# TEC-Controller.net
KiCad netlist of a schematic drawn in EAGLE
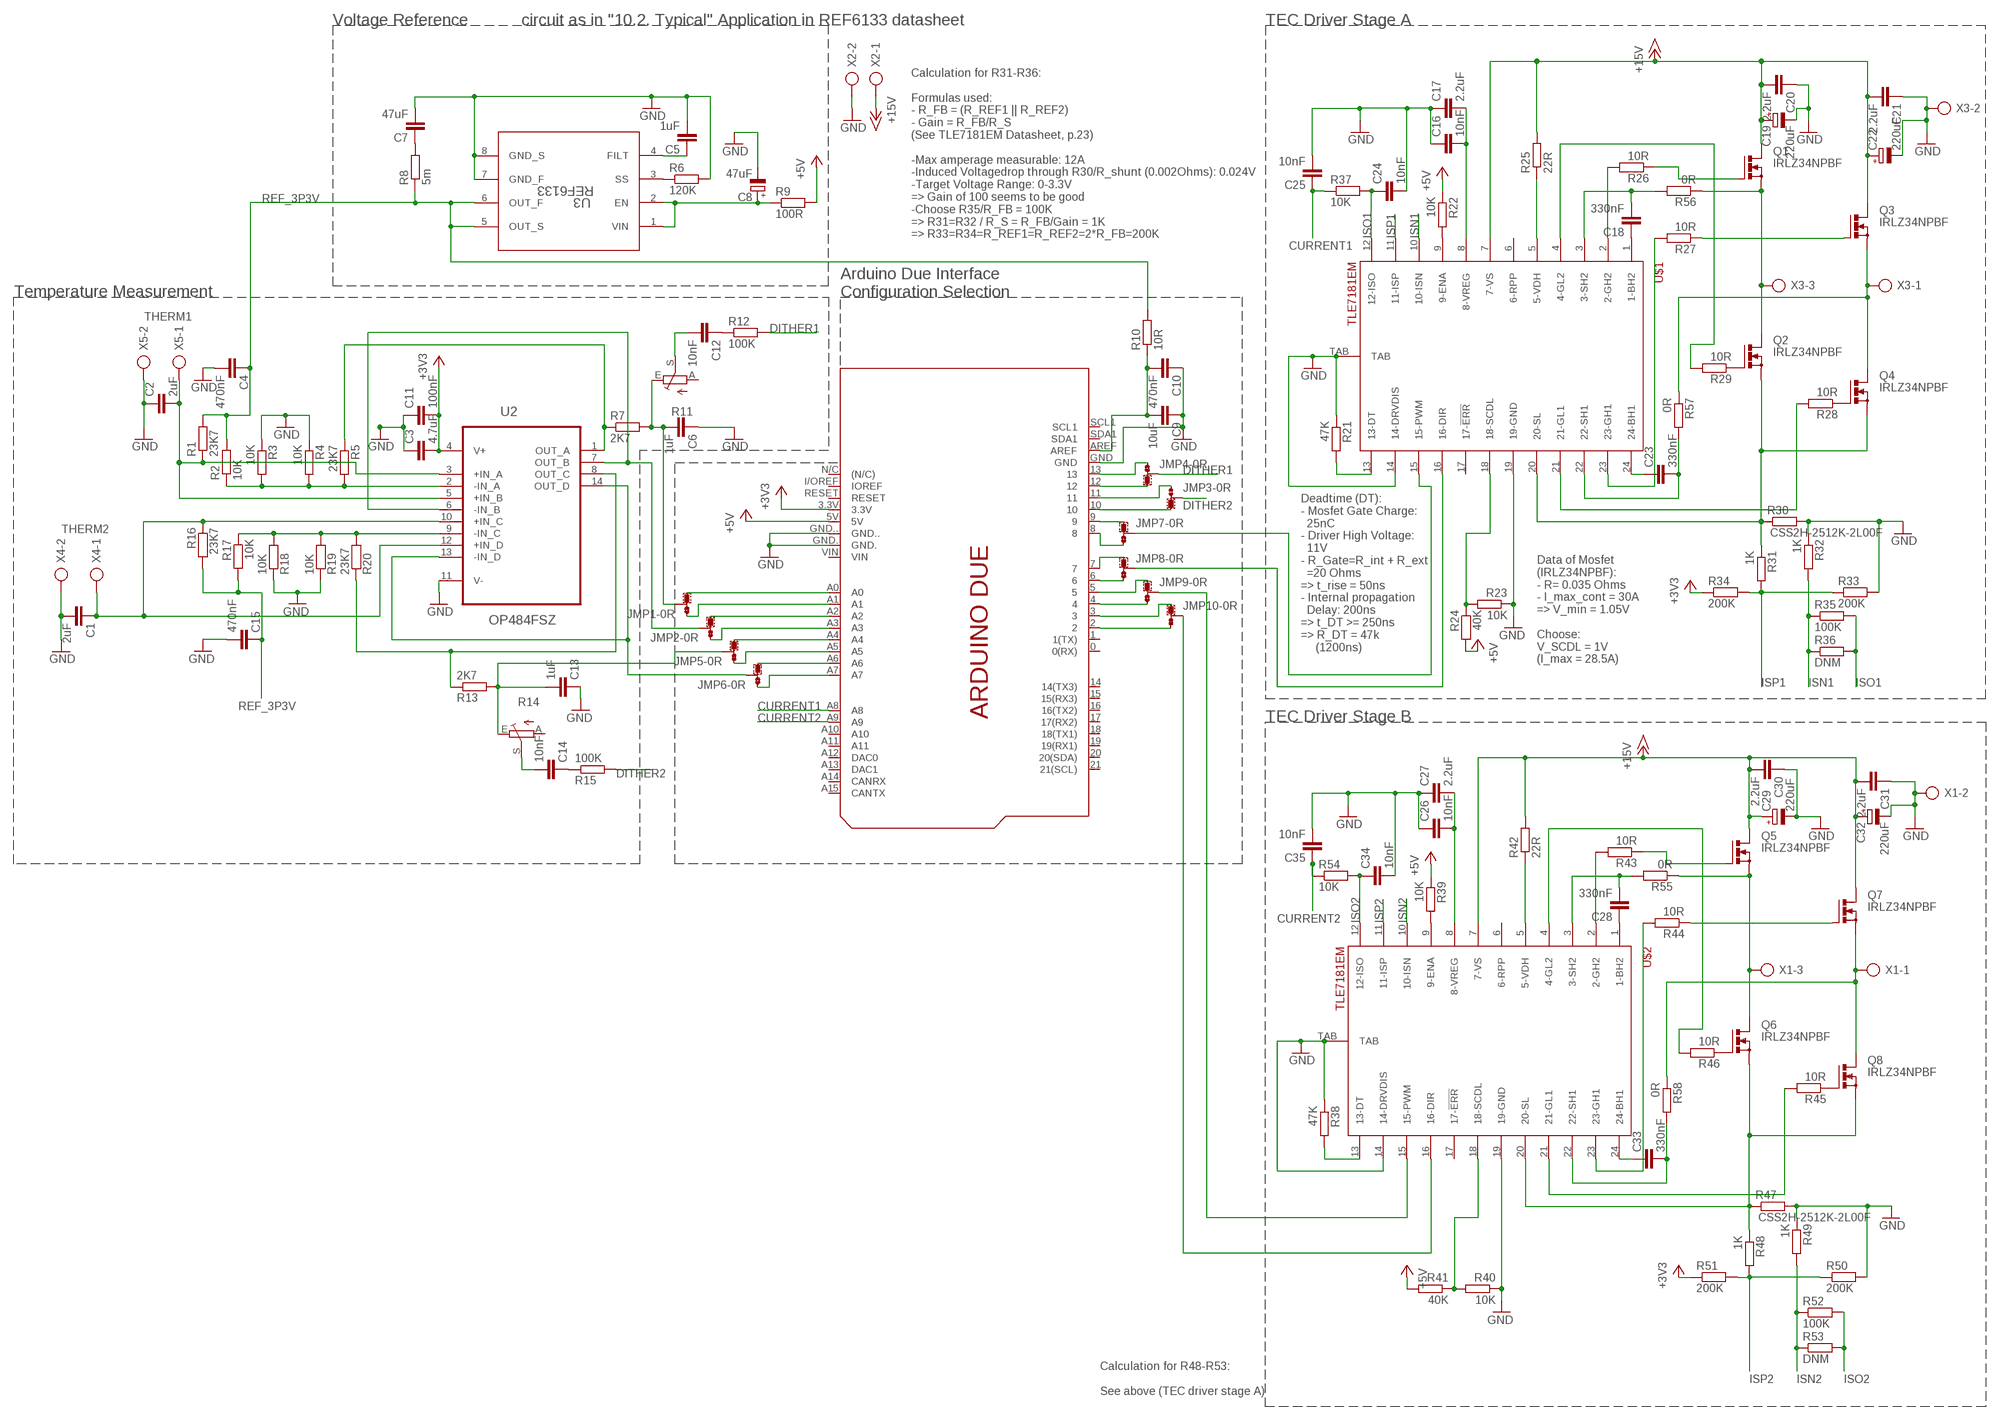
[diagram p0: schematic, sheet 1]

(export (version "E")
  (design (tool "Eeschema 10.0.6"))
  (components
    (comp (ref "C1")
      (value "2uF")
      (footprint "eagle-import:C0805")
      (libsource (lib "eagle-import") (part "C-EUC0805"))
    )
    (comp (ref "C2")
      (value "2uF")
      (footprint "eagle-import:C0805")
      (libsource (lib "eagle-import") (part "C-EUC0805"))
    )
    (comp (ref "C3")
      (value "4.7uF")
      (footprint "eagle-import:C0603")
      (libsource (lib "eagle-import") (part "C-EUC0603"))
    )
    (comp (ref "C4")
      (value "470nF")
      (footprint "eagle-import:C0805")
      (libsource (lib "eagle-import") (part "C-EUC0805"))
    )
    (comp (ref "C5")
      (value "1uF")
      (footprint "eagle-import:C0805")
      (libsource (lib "eagle-import") (part "C-EUC0805"))
    )
    (comp (ref "C6")
      (value "1uF")
      (footprint "eagle-import:C0805")
      (libsource (lib "eagle-import") (part "C-EUC0805"))
    )
    (comp (ref "C7")
      (value "47uF")
      (footprint "eagle-import:C0603")
      (libsource (lib "eagle-import") (part "C-EUC0603"))
    )
    (comp (ref "C8")
      (value "47uF")
      (footprint "eagle-import:PANASONIC_D")
      (libsource (lib "eagle-import") (part "CPOL-EUD"))
    )
    (comp (ref "C9")
      (value "10uF")
      (footprint "eagle-import:C0603")
      (libsource (lib "eagle-import") (part "C-EUC0603"))
    )
    (comp (ref "C10")
      (value "470nF")
      (footprint "eagle-import:C0603")
      (libsource (lib "eagle-import") (part "C-EUC0603"))
    )
    (comp (ref "C11")
      (value "100nF")
      (footprint "eagle-import:C0603")
      (libsource (lib "eagle-import") (part "C-EUC0603"))
    )
    (comp (ref "C12")
      (value "10nF")
      (footprint "eagle-import:C0805")
      (libsource (lib "eagle-import") (part "C-EUC0805"))
    )
    (comp (ref "C13")
      (value "1uF")
      (footprint "eagle-import:C0805")
      (libsource (lib "eagle-import") (part "C-EUC0805"))
    )
    (comp (ref "C14")
      (value "10nF")
      (footprint "eagle-import:C0805")
      (libsource (lib "eagle-import") (part "C-EUC0805"))
    )
    (comp (ref "C15")
      (value "470nF")
      (footprint "eagle-import:C0603")
      (libsource (lib "eagle-import") (part "C-EUC0603"))
    )
    (comp (ref "C16")
      (value "10nF")
      (footprint "eagle-import:C0603K")
      (libsource (lib "eagle-import") (part "C-EUC0603K"))
    )
    (comp (ref "C17")
      (value "2.2uF")
      (footprint "eagle-import:C0603K")
      (libsource (lib "eagle-import") (part "C-EUC0603K"))
    )
    (comp (ref "C18")
      (value "330nF")
      (footprint "eagle-import:C0603K")
      (libsource (lib "eagle-import") (part "C-EUC0603K"))
    )
    (comp (ref "C19")
      (value "220uF")
      (footprint "eagle-import:E2,5-7")
      (libsource (lib "eagle-import") (part "CPOL-EUE2.5-7"))
    )
    (comp (ref "C20")
      (value "2.2uF")
      (footprint "eagle-import:C0603K")
      (libsource (lib "eagle-import") (part "C-EUC0603K"))
    )
    (comp (ref "C21")
      (value "2.2uF")
      (footprint "eagle-import:C0603K")
      (libsource (lib "eagle-import") (part "C-EUC0603K"))
    )
    (comp (ref "C22")
      (value "220uF")
      (footprint "eagle-import:E2,5-7")
      (libsource (lib "eagle-import") (part "CPOL-EUE2.5-7"))
    )
    (comp (ref "C23")
      (value "330nF")
      (footprint "eagle-import:C0603K")
      (libsource (lib "eagle-import") (part "C-EUC0603K"))
    )
    (comp (ref "C24")
      (value "10nF")
      (footprint "eagle-import:C0603K")
      (libsource (lib "eagle-import") (part "C-EUC0603K"))
    )
    (comp (ref "C25")
      (value "10nF")
      (footprint "eagle-import:C0603K")
      (libsource (lib "eagle-import") (part "C-EUC0603K"))
    )
    (comp (ref "C26")
      (value "10nF")
      (footprint "eagle-import:C0603")
      (libsource (lib "eagle-import") (part "C-EUC0603"))
    )
    (comp (ref "C27")
      (value "2.2uF")
      (footprint "eagle-import:C0603")
      (libsource (lib "eagle-import") (part "C-EUC0603"))
    )
    (comp (ref "C28")
      (value "330nF")
      (footprint "eagle-import:C0603K")
      (libsource (lib "eagle-import") (part "C-EUC0603K"))
    )
    (comp (ref "C29")
      (value "220uF")
      (footprint "eagle-import:E2,5-7")
      (libsource (lib "eagle-import") (part "CPOL-EUE2.5-7"))
    )
    (comp (ref "C30")
      (value "2.2uF")
      (footprint "eagle-import:C0603K")
      (libsource (lib "eagle-import") (part "C-EUC0603K"))
    )
    (comp (ref "C31")
      (value "2.2uF")
      (footprint "eagle-import:C0603K")
      (libsource (lib "eagle-import") (part "C-EUC0603K"))
    )
    (comp (ref "C32")
      (value "220uF")
      (footprint "eagle-import:E2,5-7")
      (libsource (lib "eagle-import") (part "CPOL-EUE2.5-7"))
    )
    (comp (ref "C33")
      (value "330nF")
      (footprint "eagle-import:C0603K")
      (libsource (lib "eagle-import") (part "C-EUC0603K"))
    )
    (comp (ref "C34")
      (value "10nF")
      (footprint "eagle-import:C0603")
      (libsource (lib "eagle-import") (part "C-EUC0603"))
    )
    (comp (ref "C35")
      (value "10nF")
      (footprint "eagle-import:C0603")
      (libsource (lib "eagle-import") (part "C-EUC0603"))
    )
    (comp (ref "JMP1")
      (value "0R-JUMPA")
      (footprint "eagle-import:A0R-JMP")
      (libsource (lib "eagle-import") (part "0R-JUMPA"))
    )
    (comp (ref "JMP2")
      (value "0R-JUMPA")
      (footprint "eagle-import:A0R-JMP")
      (libsource (lib "eagle-import") (part "0R-JUMPA"))
    )
    (comp (ref "JMP3")
      (value "0R-JUMPA")
      (footprint "eagle-import:A0R-JMP")
      (libsource (lib "eagle-import") (part "0R-JUMPA"))
    )
    (comp (ref "JMP4")
      (value "0R-JUMPA")
      (footprint "eagle-import:A0R-JMP")
      (libsource (lib "eagle-import") (part "0R-JUMPA"))
    )
    (comp (ref "JMP5")
      (value "0R-JUMPA")
      (footprint "eagle-import:A0R-JMP")
      (libsource (lib "eagle-import") (part "0R-JUMPA"))
    )
    (comp (ref "JMP6")
      (value "0R-JUMPA")
      (footprint "eagle-import:A0R-JMP")
      (libsource (lib "eagle-import") (part "0R-JUMPA"))
    )
    (comp (ref "JMP7")
      (value "0R-JUMPA")
      (footprint "eagle-import:A0R-JMP")
      (libsource (lib "eagle-import") (part "0R-JUMPA"))
    )
    (comp (ref "JMP8")
      (value "0R-JUMPA")
      (footprint "eagle-import:A0R-JMP")
      (libsource (lib "eagle-import") (part "0R-JUMPA"))
    )
    (comp (ref "JMP9")
      (value "0R-JUMPA")
      (footprint "eagle-import:A0R-JMP")
      (libsource (lib "eagle-import") (part "0R-JUMPA"))
    )
    (comp (ref "JMP10")
      (value "0R-JUMPA")
      (footprint "eagle-import:A0R-JMP")
      (libsource (lib "eagle-import") (part "0R-JUMPA"))
    )
    (comp (ref "PCB1")
      (value "ARDUINO_DUE_SHIELD")
      (footprint "eagle-import:ARDUINO_DUE_SHIELD")
      (libsource (lib "eagle-import") (part "ARDUINO_DUE_SHIELD"))
    )
    (comp (ref "Q1")
      (value "IRLZ34NPBF")
      (footprint "eagle-import:TO220BV")
      (libsource (lib "eagle-import") (part "PMOSFET_NTO220BV"))
    )
    (comp (ref "Q2")
      (value "IRLZ34NPBF")
      (footprint "eagle-import:TO220BV")
      (libsource (lib "eagle-import") (part "PMOSFET_NTO220BV"))
    )
    (comp (ref "Q3")
      (value "IRLZ34NPBF")
      (footprint "eagle-import:TO220BV")
      (libsource (lib "eagle-import") (part "PMOSFET_NTO220BV"))
    )
    (comp (ref "Q4")
      (value "IRLZ34NPBF")
      (footprint "eagle-import:TO220BV")
      (libsource (lib "eagle-import") (part "PMOSFET_NTO220BV"))
    )
    (comp (ref "Q5")
      (value "IRLZ34NPBF")
      (footprint "eagle-import:TO220BV")
      (libsource (lib "eagle-import") (part "PMOSFET_NTO220BV"))
    )
    (comp (ref "Q6")
      (value "IRLZ34NPBF")
      (footprint "eagle-import:TO220BV")
      (libsource (lib "eagle-import") (part "PMOSFET_NTO220BV"))
    )
    (comp (ref "Q7")
      (value "IRLZ34NPBF")
      (footprint "eagle-import:TO220BV")
      (libsource (lib "eagle-import") (part "PMOSFET_NTO220BV"))
    )
    (comp (ref "Q8")
      (value "IRLZ34NPBF")
      (footprint "eagle-import:TO220BV")
      (libsource (lib "eagle-import") (part "PMOSFET_NTO220BV"))
    )
    (comp (ref "R1")
      (value "23K7")
      (footprint "eagle-import:R0603")
      (libsource (lib "eagle-import") (part "R-EU_R0603"))
    )
    (comp (ref "R2")
      (value "10K")
      (footprint "eagle-import:R0603")
      (libsource (lib "eagle-import") (part "R-EU_R0603"))
    )
    (comp (ref "R3")
      (value "10K")
      (footprint "eagle-import:R0603")
      (libsource (lib "eagle-import") (part "R-EU_R0603"))
    )
    (comp (ref "R4")
      (value "10K")
      (footprint "eagle-import:R0805")
      (libsource (lib "eagle-import") (part "R-EU_R0805"))
    )
    (comp (ref "R5")
      (value "23K7")
      (footprint "eagle-import:R0805")
      (libsource (lib "eagle-import") (part "R-EU_R0805"))
    )
    (comp (ref "R6")
      (value "120K")
      (footprint "eagle-import:R0805")
      (libsource (lib "eagle-import") (part "R-EU_R0805"))
    )
    (comp (ref "R7")
      (value "2K7")
      (footprint "eagle-import:R0805")
      (libsource (lib "eagle-import") (part "R-EU_R0805"))
    )
    (comp (ref "R8")
      (value "5m")
      (footprint "eagle-import:R0603")
      (libsource (lib "eagle-import") (part "R-EU_R0603"))
    )
    (comp (ref "R9")
      (value "100R")
      (footprint "eagle-import:R0805")
      (libsource (lib "eagle-import") (part "R-EU_R0805"))
    )
    (comp (ref "R10")
      (value "10R")
      (footprint "eagle-import:R0805")
      (libsource (lib "eagle-import") (part "R-EU_R0805"))
    )
    (comp (ref "R11")
      (value "TRIM_EU-B64W")
      (footprint "eagle-import:B64W")
      (libsource (lib "eagle-import") (part "TRIM_EU-B64W"))
    )
    (comp (ref "R12")
      (value "100K")
      (footprint "eagle-import:R0805")
      (libsource (lib "eagle-import") (part "R-EU_R0805"))
    )
    (comp (ref "R13")
      (value "2K7")
      (footprint "eagle-import:R0805")
      (libsource (lib "eagle-import") (part "R-EU_R0805"))
    )
    (comp (ref "R14")
      (value "TRIM_EU-B64W")
      (footprint "eagle-import:B64W")
      (libsource (lib "eagle-import") (part "TRIM_EU-B64W"))
    )
    (comp (ref "R15")
      (value "100K")
      (footprint "eagle-import:R0805")
      (libsource (lib "eagle-import") (part "R-EU_R0805"))
    )
    (comp (ref "R16")
      (value "23K7")
      (footprint "eagle-import:R0805")
      (libsource (lib "eagle-import") (part "R-EU_R0805"))
    )
    (comp (ref "R17")
      (value "10K")
      (footprint "eagle-import:R0805")
      (libsource (lib "eagle-import") (part "R-EU_R0805"))
    )
    (comp (ref "R18")
      (value "10K")
      (footprint "eagle-import:R0805")
      (libsource (lib "eagle-import") (part "R-EU_R0805"))
    )
    (comp (ref "R19")
      (value "10K")
      (footprint "eagle-import:R0805")
      (libsource (lib "eagle-import") (part "R-EU_R0805"))
    )
    (comp (ref "R20")
      (value "23K7")
      (footprint "eagle-import:R0805")
      (libsource (lib "eagle-import") (part "R-EU_R0805"))
    )
    (comp (ref "R21")
      (value "47K")
      (footprint "eagle-import:R0603")
      (libsource (lib "eagle-import") (part "R-EU_R0603"))
    )
    (comp (ref "R22")
      (value "10K")
      (footprint "eagle-import:R0603")
      (libsource (lib "eagle-import") (part "R-EU_R0603"))
    )
    (comp (ref "R23")
      (value "10K")
      (footprint "eagle-import:R0603")
      (libsource (lib "eagle-import") (part "R-EU_R0603"))
    )
    (comp (ref "R24")
      (value "40K")
      (footprint "eagle-import:R0603")
      (libsource (lib "eagle-import") (part "R-EU_R0603"))
    )
    (comp (ref "R25")
      (value "22R")
      (footprint "eagle-import:R0603")
      (libsource (lib "eagle-import") (part "R-EU_R0603"))
    )
    (comp (ref "R26")
      (value "10R")
      (footprint "eagle-import:R0805")
      (libsource (lib "eagle-import") (part "R-EU_R0805"))
    )
    (comp (ref "R27")
      (value "10R")
      (footprint "eagle-import:0204_7")
      (libsource (lib "eagle-import") (part "R-EU_0204/7"))
    )
    (comp (ref "R28")
      (value "10R")
      (footprint "eagle-import:0204_7")
      (libsource (lib "eagle-import") (part "R-EU_0204/7"))
    )
    (comp (ref "R29")
      (value "10R")
      (footprint "eagle-import:0204_7")
      (libsource (lib "eagle-import") (part "R-EU_0204/7"))
    )
    (comp (ref "R30")
      (value "CSS2H-2512K-2L00F")
      (footprint "eagle-import:R2512")
      (libsource (lib "eagle-import") (part "R-EU_R2512"))
    )
    (comp (ref "R31")
      (value "1K")
      (footprint "eagle-import:R0603")
      (libsource (lib "eagle-import") (part "R-EU_R0603"))
    )
    (comp (ref "R32")
      (value "1K")
      (footprint "eagle-import:R0603")
      (libsource (lib "eagle-import") (part "R-EU_R0603"))
    )
    (comp (ref "R33")
      (value "200K")
      (footprint "eagle-import:R0603")
      (libsource (lib "eagle-import") (part "R-EU_R0603"))
    )
    (comp (ref "R34")
      (value "200K")
      (footprint "eagle-import:R0603")
      (libsource (lib "eagle-import") (part "R-EU_R0603"))
    )
    (comp (ref "R35")
      (value "100K")
      (footprint "eagle-import:R0603")
      (libsource (lib "eagle-import") (part "R-EU_R0603"))
    )
    (comp (ref "R36")
      (value "DNM")
      (footprint "eagle-import:R0603")
      (libsource (lib "eagle-import") (part "R-EU_R0603"))
    )
    (comp (ref "R37")
      (value "10K")
      (footprint "eagle-import:R0603")
      (libsource (lib "eagle-import") (part "R-EU_R0603"))
    )
    (comp (ref "R38")
      (value "47K")
      (footprint "eagle-import:R0603")
      (libsource (lib "eagle-import") (part "R-EU_R0603"))
    )
    (comp (ref "R39")
      (value "10K")
      (footprint "eagle-import:R0603")
      (libsource (lib "eagle-import") (part "R-EU_R0603"))
    )
    (comp (ref "R40")
      (value "10K")
      (footprint "eagle-import:R0603")
      (libsource (lib "eagle-import") (part "R-EU_R0603"))
    )
    (comp (ref "R41")
      (value "40K")
      (footprint "eagle-import:R0603")
      (libsource (lib "eagle-import") (part "R-EU_R0603"))
    )
    (comp (ref "R42")
      (value "22R")
      (footprint "eagle-import:R0603")
      (libsource (lib "eagle-import") (part "R-EU_R0603"))
    )
    (comp (ref "R43")
      (value "10R")
      (footprint "eagle-import:0204_7")
      (libsource (lib "eagle-import") (part "R-EU_0204/7"))
    )
    (comp (ref "R44")
      (value "10R")
      (footprint "eagle-import:0204_7")
      (libsource (lib "eagle-import") (part "R-EU_0204/7"))
    )
    (comp (ref "R45")
      (value "10R")
      (footprint "eagle-import:0204_7")
      (libsource (lib "eagle-import") (part "R-EU_0204/7"))
    )
    (comp (ref "R46")
      (value "10R")
      (footprint "eagle-import:0204_7")
      (libsource (lib "eagle-import") (part "R-EU_0204/7"))
    )
    (comp (ref "R47")
      (value "CSS2H-2512K-2L00F")
      (footprint "eagle-import:R2512")
      (libsource (lib "eagle-import") (part "R-EU_R2512"))
    )
    (comp (ref "R48")
      (value "1K")
      (footprint "eagle-import:R0603")
      (libsource (lib "eagle-import") (part "R-EU_R0603"))
    )
    (comp (ref "R49")
      (value "1K")
      (footprint "eagle-import:R0603")
      (libsource (lib "eagle-import") (part "R-EU_R0603"))
    )
    (comp (ref "R50")
      (value "200K")
      (footprint "eagle-import:R0603")
      (libsource (lib "eagle-import") (part "R-EU_R0603"))
    )
    (comp (ref "R51")
      (value "200K")
      (footprint "eagle-import:R0603")
      (libsource (lib "eagle-import") (part "R-EU_R0603"))
    )
    (comp (ref "R52")
      (value "100K")
      (footprint "eagle-import:R0603")
      (libsource (lib "eagle-import") (part "R-EU_R0603"))
    )
    (comp (ref "R53")
      (value "DNM")
      (footprint "eagle-import:R0603")
      (libsource (lib "eagle-import") (part "R-EU_R0603"))
    )
    (comp (ref "R54")
      (value "10K")
      (footprint "eagle-import:R0603")
      (libsource (lib "eagle-import") (part "R-EU_R0603"))
    )
    (comp (ref "R55")
      (value "0R")
      (footprint "eagle-import:0204_7")
      (libsource (lib "eagle-import") (part "R-EU_0204/7"))
    )
    (comp (ref "R56")
      (value "0R")
      (footprint "eagle-import:0204_7")
      (libsource (lib "eagle-import") (part "R-EU_0204/7"))
    )
    (comp (ref "R57")
      (value "0R")
      (footprint "eagle-import:0204_7")
      (libsource (lib "eagle-import") (part "R-EU_0204/7"))
    )
    (comp (ref "R58")
      (value "0R")
      (footprint "eagle-import:0204_7")
      (libsource (lib "eagle-import") (part "R-EU_0204/7"))
    )
    (comp (ref "U$1")
      (value "TLE7181EM")
      (footprint "eagle-import:PG-SSOP-24-4")
      (libsource (lib "eagle-import") (part "TLE7181EM"))
    )
    (comp (ref "U$2")
      (value "TLE7181EM")
      (footprint "eagle-import:PG-SSOP-24-4")
      (libsource (lib "eagle-import") (part "TLE7181EM"))
    )
    (comp (ref "U2")
      (value "OP484FSZ")
      (footprint "eagle-import:SOIC127P600X175-14N")
      (libsource (lib "eagle-import") (part "OP484FSZ"))
    )
    (comp (ref "U3")
      (value "REF6133")
      (footprint "eagle-import:DGK0008A_N")
      (fields (field (name "MANUFACTURER") "Texas Instruments") (field (name "PARTNUMBER") "REF6033IDGKR"))
      (libsource (lib "eagle-import") (part "REF6033IDGKR"))
    )
    (comp (ref "X1")
      (value "AK500/3")
      (footprint "eagle-import:AK500_3")
      (libsource (lib "eagle-import") (part "AK500/3"))
    )
    (comp (ref "X2")
      (value "AK500/2")
      (footprint "eagle-import:AK500_2")
      (libsource (lib "eagle-import") (part "AK500/2"))
    )
    (comp (ref "X3")
      (value "AK500/3")
      (footprint "eagle-import:AK500_3")
      (libsource (lib "eagle-import") (part "AK500/3"))
    )
    (comp (ref "X4")
      (value "AK500/2")
      (footprint "eagle-import:AK500_2")
      (libsource (lib "eagle-import") (part "AK500/2"))
    )
    (comp (ref "X5")
      (value "AK500/2")
      (footprint "eagle-import:AK500_2")
      (libsource (lib "eagle-import") (part "AK500/2"))
    )
  )
  (nets
    (net (code "1") (name "+3V3") (class "Default")
      (node (ref "C11") (pin "2") (pinfunction "2_2") (pintype "passive"))
      (node (ref "C3") (pin "2") (pinfunction "2_2") (pintype "passive"))
      (node (ref "PCB1") (pin "3.3V") (pinfunction "3.3V_3.3V") (pintype "bidirectional"))
      (node (ref "R34") (pin "1") (pinfunction "1_1") (pintype "passive"))
      (node (ref "R51") (pin "1") (pinfunction "1_1") (pintype "passive"))
      (node (ref "U2") (pin "4") (pinfunction "V+_4") (pintype "power_in"))
    )
    (net (code "2") (name "+5V") (class "Default")
      (node (ref "PCB1") (pin "5V") (pinfunction "5V_5V") (pintype "bidirectional"))
      (node (ref "R22") (pin "1") (pinfunction "1_1") (pintype "passive"))
      (node (ref "R24") (pin "2") (pinfunction "2_2") (pintype "passive"))
      (node (ref "R39") (pin "1") (pinfunction "1_1") (pintype "passive"))
      (node (ref "R41") (pin "2") (pinfunction "2_2") (pintype "passive"))
      (node (ref "R9") (pin "2") (pinfunction "2_2") (pintype "passive"))
    )
    (net (code "3") (name "+15V") (class "Default")
      (node (ref "C19") (pin "+") (pinfunction "+_+") (pintype "passive"))
      (node (ref "C20") (pin "2") (pinfunction "2_2") (pintype "passive"))
      (node (ref "C21") (pin "2") (pinfunction "2_2") (pintype "passive"))
      (node (ref "C22") (pin "+") (pinfunction "+_+") (pintype "passive"))
      (node (ref "C29") (pin "+") (pinfunction "+_+") (pintype "passive"))
      (node (ref "C30") (pin "2") (pinfunction "2_2") (pintype "passive"))
      (node (ref "C31") (pin "2") (pinfunction "2_2") (pintype "passive"))
      (node (ref "C32") (pin "+") (pinfunction "+_+") (pintype "passive"))
      (node (ref "Q1") (pin "D") (pinfunction "D_D") (pintype "passive"))
      (node (ref "Q3") (pin "D") (pinfunction "D_D") (pintype "passive"))
      (node (ref "Q5") (pin "D") (pinfunction "D_D") (pintype "passive"))
      (node (ref "Q7") (pin "D") (pinfunction "D_D") (pintype "passive"))
      (node (ref "R25") (pin "2") (pinfunction "2_2") (pintype "passive"))
      (node (ref "R42") (pin "2") (pinfunction "2_2") (pintype "passive"))
      (node (ref "U$1") (pin "7") (pinfunction "7-VS_7") (pintype "bidirectional"))
      (node (ref "U$2") (pin "7") (pinfunction "7-VS_7") (pintype "bidirectional"))
      (node (ref "X2") (pin "1") (pinfunction "KL_1") (pintype "passive"))
    )
    (net (code "4") (name "/CURRENT1") (class "Default")
      (node (ref "C25") (pin "1") (pinfunction "1_1") (pintype "passive"))
      (node (ref "PCB1") (pin "A8") (pinfunction "A8_A8") (pintype "bidirectional"))
      (node (ref "R37") (pin "1") (pinfunction "1_1") (pintype "passive"))
    )
    (net (code "5") (name "/CURRENT2") (class "Default")
      (node (ref "C35") (pin "1") (pinfunction "1_1") (pintype "passive"))
      (node (ref "PCB1") (pin "A9") (pinfunction "A9_A9") (pintype "bidirectional"))
      (node (ref "R54") (pin "1") (pinfunction "1_1") (pintype "passive"))
    )
    (net (code "6") (name "/DITHER1") (class "Default")
      (node (ref "JMP4") (pin "2") (pinfunction "2_2") (pintype "passive"))
      (node (ref "R12") (pin "2") (pinfunction "2_2") (pintype "passive"))
    )
    (net (code "7") (name "/DITHER2") (class "Default")
      (node (ref "JMP3") (pin "2") (pinfunction "2_2") (pintype "passive"))
      (node (ref "R15") (pin "2") (pinfunction "2_2") (pintype "passive"))
    )
    (net (code "8") (name "/ISN1") (class "Default")
      (node (ref "R32") (pin "2") (pinfunction "2_2") (pintype "passive"))
      (node (ref "R35") (pin "1") (pinfunction "1_1") (pintype "passive"))
      (node (ref "R36") (pin "1") (pinfunction "1_1") (pintype "passive"))
      (node (ref "U$1") (pin "10") (pinfunction "10-ISN_10") (pintype "bidirectional"))
    )
    (net (code "9") (name "/ISN2") (class "Default")
      (node (ref "R49") (pin "2") (pinfunction "2_2") (pintype "passive"))
      (node (ref "R52") (pin "1") (pinfunction "1_1") (pintype "passive"))
      (node (ref "R53") (pin "1") (pinfunction "1_1") (pintype "passive"))
      (node (ref "U$2") (pin "10") (pinfunction "10-ISN_10") (pintype "bidirectional"))
    )
    (net (code "10") (name "/ISO1") (class "Default")
      (node (ref "C24") (pin "1") (pinfunction "1_1") (pintype "passive"))
      (node (ref "R35") (pin "2") (pinfunction "2_2") (pintype "passive"))
      (node (ref "R36") (pin "2") (pinfunction "2_2") (pintype "passive"))
      (node (ref "R37") (pin "2") (pinfunction "2_2") (pintype "passive"))
      (node (ref "U$1") (pin "12") (pinfunction "12-ISO_12") (pintype "bidirectional"))
    )
    (net (code "11") (name "/ISO2") (class "Default")
      (node (ref "C34") (pin "1") (pinfunction "1_1") (pintype "passive"))
      (node (ref "R52") (pin "2") (pinfunction "2_2") (pintype "passive"))
      (node (ref "R53") (pin "2") (pinfunction "2_2") (pintype "passive"))
      (node (ref "R54") (pin "2") (pinfunction "2_2") (pintype "passive"))
      (node (ref "U$2") (pin "12") (pinfunction "12-ISO_12") (pintype "bidirectional"))
    )
    (net (code "12") (name "/ISP1") (class "Default")
      (node (ref "R31") (pin "2") (pinfunction "2_2") (pintype "passive"))
      (node (ref "R33") (pin "1") (pinfunction "1_1") (pintype "passive"))
      (node (ref "R34") (pin "2") (pinfunction "2_2") (pintype "passive"))
      (node (ref "U$1") (pin "11") (pinfunction "11-ISP_11") (pintype "bidirectional"))
    )
    (net (code "13") (name "/ISP2") (class "Default")
      (node (ref "R48") (pin "2") (pinfunction "2_2") (pintype "passive"))
      (node (ref "R50") (pin "1") (pinfunction "1_1") (pintype "passive"))
      (node (ref "R51") (pin "2") (pinfunction "2_2") (pintype "passive"))
      (node (ref "U$2") (pin "11") (pinfunction "11-ISP_11") (pintype "bidirectional"))
    )
    (net (code "14") (name "/REF_3P3V") (class "Default")
      (node (ref "C15") (pin "1") (pinfunction "1_1") (pintype "passive"))
      (node (ref "C4") (pin "1") (pinfunction "1_1") (pintype "passive"))
      (node (ref "R1") (pin "2") (pinfunction "2_2") (pintype "passive"))
      (node (ref "R10") (pin "2") (pinfunction "2_2") (pintype "passive"))
      (node (ref "R16") (pin "2") (pinfunction "2_2") (pintype "passive"))
      (node (ref "R17") (pin "2") (pinfunction "2_2") (pintype "passive"))
      (node (ref "R2") (pin "2") (pinfunction "2_2") (pintype "passive"))
      (node (ref "R8") (pin "1") (pinfunction "1_1") (pintype "passive"))
      (node (ref "U3") (pin "5") (pinfunction "OUT_S_5") (pintype "passive"))
      (node (ref "U3") (pin "6") (pinfunction "OUT_F_6") (pintype "passive"))
    )
    (net (code "15") (name "GND") (class "Default")
      (node (ref "C1") (pin "2") (pinfunction "2_2") (pintype "passive"))
      (node (ref "C10") (pin "1") (pinfunction "1_1") (pintype "passive"))
      (node (ref "C11") (pin "1") (pinfunction "1_1") (pintype "passive"))
      (node (ref "C13") (pin "1") (pinfunction "1_1") (pintype "passive"))
      (node (ref "C15") (pin "2") (pinfunction "2_2") (pintype "passive"))
      (node (ref "C16") (pin "1") (pinfunction "1_1") (pintype "passive"))
      (node (ref "C17") (pin "1") (pinfunction "1_1") (pintype "passive"))
      (node (ref "C19") (pin "-") (pinfunction "-_-") (pintype "passive"))
      (node (ref "C2") (pin "1") (pinfunction "1_1") (pintype "passive"))
      (node (ref "C20") (pin "1") (pinfunction "1_1") (pintype "passive"))
      (node (ref "C21") (pin "1") (pinfunction "1_1") (pintype "passive"))
      (node (ref "C22") (pin "-") (pinfunction "-_-") (pintype "passive"))
      (node (ref "C24") (pin "2") (pinfunction "2_2") (pintype "passive"))
      (node (ref "C25") (pin "2") (pinfunction "2_2") (pintype "passive"))
      (node (ref "C26") (pin "1") (pinfunction "1_1") (pintype "passive"))
      (node (ref "C27") (pin "1") (pinfunction "1_1") (pintype "passive"))
      (node (ref "C29") (pin "-") (pinfunction "-_-") (pintype "passive"))
      (node (ref "C3") (pin "1") (pinfunction "1_1") (pintype "passive"))
      (node (ref "C30") (pin "1") (pinfunction "1_1") (pintype "passive"))
      (node (ref "C31") (pin "1") (pinfunction "1_1") (pintype "passive"))
      (node (ref "C32") (pin "-") (pinfunction "-_-") (pintype "passive"))
      (node (ref "C34") (pin "2") (pinfunction "2_2") (pintype "passive"))
      (node (ref "C35") (pin "2") (pinfunction "2_2") (pintype "passive"))
      (node (ref "C4") (pin "2") (pinfunction "2_2") (pintype "passive"))
      (node (ref "C5") (pin "2") (pinfunction "2_2") (pintype "passive"))
      (node (ref "C6") (pin "1") (pinfunction "1_1") (pintype "passive"))
      (node (ref "C7") (pin "2") (pinfunction "2_2") (pintype "passive"))
      (node (ref "C8") (pin "-") (pinfunction "-_-") (pintype "passive"))
      (node (ref "C9") (pin "1") (pinfunction "1_1") (pintype "passive"))
      (node (ref "PCB1") (pin "GND") (pinfunction "GND_GND") (pintype "bidirectional"))
      (node (ref "PCB1") (pin "GND.") (pinfunction "GND._GND.") (pintype "bidirectional"))
      (node (ref "PCB1") (pin "GND..") (pinfunction "GND.._GND..") (pintype "bidirectional"))
      (node (ref "R18") (pin "1") (pinfunction "1_1") (pintype "passive"))
      (node (ref "R19") (pin "1") (pinfunction "1_1") (pintype "passive"))
      (node (ref "R21") (pin "1") (pinfunction "1_1") (pintype "passive"))
      (node (ref "R23") (pin "1") (pinfunction "1_1") (pintype "passive"))
      (node (ref "R3") (pin "1") (pinfunction "1_1") (pintype "passive"))
      (node (ref "R30") (pin "2") (pinfunction "2_2") (pintype "passive"))
      (node (ref "R32") (pin "1") (pinfunction "1_1") (pintype "passive"))
      (node (ref "R33") (pin "2") (pinfunction "2_2") (pintype "passive"))
      (node (ref "R38") (pin "1") (pinfunction "1_1") (pintype "passive"))
      (node (ref "R4") (pin "1") (pinfunction "1_1") (pintype "passive"))
      (node (ref "R40") (pin "1") (pinfunction "1_1") (pintype "passive"))
      (node (ref "R47") (pin "2") (pinfunction "2_2") (pintype "passive"))
      (node (ref "R49") (pin "1") (pinfunction "1_1") (pintype "passive"))
      (node (ref "R50") (pin "2") (pinfunction "2_2") (pintype "passive"))
      (node (ref "R6") (pin "2") (pinfunction "2_2") (pintype "passive"))
      (node (ref "U$1") (pin "14") (pinfunction "14-DRVDIS_14") (pintype "bidirectional"))
      (node (ref "U$1") (pin "19") (pinfunction "19-GND_19") (pintype "bidirectional"))
      (node (ref "U$1") (pin "TAB") (pinfunction "TAB_TAB") (pintype "bidirectional"))
      (node (ref "U$2") (pin "14") (pinfunction "14-DRVDIS_14") (pintype "bidirectional"))
      (node (ref "U$2") (pin "19") (pinfunction "19-GND_19") (pintype "bidirectional"))
      (node (ref "U$2") (pin "TAB") (pinfunction "TAB_TAB") (pintype "bidirectional"))
      (node (ref "U2") (pin "11") (pinfunction "V-_11") (pintype "power_in"))
      (node (ref "U3") (pin "7") (pinfunction "GND_F_7") (pintype "power_in"))
      (node (ref "U3") (pin "8") (pinfunction "GND_S_8") (pintype "power_in"))
      (node (ref "X1") (pin "2") (pinfunction "KL_2") (pintype "passive"))
      (node (ref "X2") (pin "2") (pinfunction "KL_2") (pintype "passive"))
      (node (ref "X3") (pin "2") (pinfunction "KL_2") (pintype "passive"))
      (node (ref "X4") (pin "2") (pinfunction "KL_2") (pintype "passive"))
      (node (ref "X5") (pin "2") (pinfunction "KL_2") (pintype "passive"))
    )
    (net (code "16") (name "Net-(C6-Pad2)") (class "Default")
      (node (ref "C6") (pin "2") (pinfunction "2_2") (pintype "passive"))
      (node (ref "JMP1") (pin "2") (pinfunction "2_2") (pintype "passive"))
      (node (ref "R11") (pin "E") (pinfunction "E_E") (pintype "passive"))
      (node (ref "R7") (pin "2") (pinfunction "2_2") (pintype "passive"))
    )
    (net (code "17") (name "Net-(C7-Pad1)") (class "Default")
      (node (ref "C7") (pin "1") (pinfunction "1_1") (pintype "passive"))
      (node (ref "R8") (pin "2") (pinfunction "2_2") (pintype "passive"))
    )
    (net (code "18") (name "Net-(C10-Pad2)") (class "Default")
      (node (ref "C10") (pin "2") (pinfunction "2_2") (pintype "passive"))
      (node (ref "C9") (pin "2") (pinfunction "2_2") (pintype "passive"))
      (node (ref "PCB1") (pin "AREF") (pinfunction "AREF_AREF") (pintype "bidirectional"))
      (node (ref "R10") (pin "1") (pinfunction "1_1") (pintype "passive"))
    )
    (net (code "19") (name "Net-(C12-Pad1)") (class "Default")
      (node (ref "C12") (pin "1") (pinfunction "1_1") (pintype "passive"))
      (node (ref "R12") (pin "1") (pinfunction "1_1") (pintype "passive"))
    )
    (net (code "20") (name "Net-(C12-Pad2)") (class "Default")
      (node (ref "C12") (pin "2") (pinfunction "2_2") (pintype "passive"))
      (node (ref "R11") (pin "S") (pinfunction "S_S") (pintype "passive"))
    )
    (net (code "21") (name "Net-(C13-Pad2)") (class "Default")
      (node (ref "C13") (pin "2") (pinfunction "2_2") (pintype "passive"))
      (node (ref "JMP5") (pin "2") (pinfunction "2_2") (pintype "passive"))
      (node (ref "R13") (pin "2") (pinfunction "2_2") (pintype "passive"))
      (node (ref "R14") (pin "E") (pinfunction "E_E") (pintype "passive"))
    )
    (net (code "22") (name "Net-(C14-Pad1)") (class "Default")
      (node (ref "C14") (pin "1") (pinfunction "1_1") (pintype "passive"))
      (node (ref "R15") (pin "1") (pinfunction "1_1") (pintype "passive"))
    )
    (net (code "23") (name "Net-(C14-Pad2)") (class "Default")
      (node (ref "C14") (pin "2") (pinfunction "2_2") (pintype "passive"))
      (node (ref "R14") (pin "S") (pinfunction "S_S") (pintype "passive"))
    )
    (net (code "24") (name "Net-(JMP1-Pad1)") (class "Default")
      (node (ref "JMP1") (pin "1") (pinfunction "1_1") (pintype "passive"))
      (node (ref "PCB1") (pin "A1") (pinfunction "A1_A1") (pintype "bidirectional"))
    )
    (net (code "25") (name "Net-(JMP1-Pad3)") (class "Default")
      (node (ref "JMP1") (pin "3") (pinfunction "3_3") (pintype "passive"))
      (node (ref "PCB1") (pin "A0") (pinfunction "A0_A0") (pintype "bidirectional"))
    )
    (net (code "26") (name "Net-(JMP2-Pad1)") (class "Default")
      (node (ref "JMP2") (pin "1") (pinfunction "1_1") (pintype "passive"))
      (node (ref "PCB1") (pin "A3") (pinfunction "A3_A3") (pintype "bidirectional"))
    )
    (net (code "27") (name "Net-(JMP2-Pad3)") (class "Default")
      (node (ref "JMP2") (pin "3") (pinfunction "3_3") (pintype "passive"))
      (node (ref "PCB1") (pin "A2") (pinfunction "A2_A2") (pintype "bidirectional"))
    )
    (net (code "28") (name "Net-(JMP3-Pad1)") (class "Default")
      (node (ref "JMP3") (pin "1") (pinfunction "1_1") (pintype "passive"))
      (node (ref "PCB1") (pin "11") (pinfunction "11_11") (pintype "bidirectional"))
    )
    (net (code "29") (name "Net-(JMP3-Pad3)") (class "Default")
      (node (ref "JMP3") (pin "3") (pinfunction "3_3") (pintype "passive"))
      (node (ref "PCB1") (pin "10") (pinfunction "10_10") (pintype "bidirectional"))
    )
    (net (code "30") (name "Net-(JMP4-Pad1)") (class "Default")
      (node (ref "JMP4") (pin "1") (pinfunction "1_1") (pintype "passive"))
      (node (ref "PCB1") (pin "13") (pinfunction "13_13") (pintype "bidirectional"))
    )
    (net (code "31") (name "Net-(JMP4-Pad3)") (class "Default")
      (node (ref "JMP4") (pin "3") (pinfunction "3_3") (pintype "passive"))
      (node (ref "PCB1") (pin "12") (pinfunction "12_12") (pintype "bidirectional"))
    )
    (net (code "32") (name "Net-(JMP5-Pad1)") (class "Default")
      (node (ref "JMP5") (pin "1") (pinfunction "1_1") (pintype "passive"))
      (node (ref "PCB1") (pin "A5") (pinfunction "A5_A5") (pintype "bidirectional"))
    )
    (net (code "33") (name "Net-(JMP5-Pad3)") (class "Default")
      (node (ref "JMP5") (pin "3") (pinfunction "3_3") (pintype "passive"))
      (node (ref "PCB1") (pin "A4") (pinfunction "A4_A4") (pintype "bidirectional"))
    )
    (net (code "34") (name "Net-(JMP6-Pad1)") (class "Default")
      (node (ref "JMP6") (pin "1") (pinfunction "1_1") (pintype "passive"))
      (node (ref "PCB1") (pin "A7") (pinfunction "A7_A7") (pintype "bidirectional"))
    )
    (net (code "35") (name "Net-(JMP6-Pad3)") (class "Default")
      (node (ref "JMP6") (pin "3") (pinfunction "3_3") (pintype "passive"))
      (node (ref "PCB1") (pin "A6") (pinfunction "A6_A6") (pintype "bidirectional"))
    )
    (net (code "36") (name "Net-(JMP7-Pad1)") (class "Default")
      (node (ref "JMP7") (pin "1") (pinfunction "1_1") (pintype "passive"))
      (node (ref "PCB1") (pin "9") (pinfunction "9_9") (pintype "bidirectional"))
    )
    (net (code "37") (name "Net-(JMP7-Pad3)") (class "Default")
      (node (ref "JMP7") (pin "3") (pinfunction "3_3") (pintype "passive"))
      (node (ref "PCB1") (pin "8") (pinfunction "8_8") (pintype "bidirectional"))
    )
    (net (code "38") (name "Net-(JMP8-Pad1)") (class "Default")
      (node (ref "JMP8") (pin "1") (pinfunction "1_1") (pintype "passive"))
      (node (ref "PCB1") (pin "7") (pinfunction "7_7") (pintype "bidirectional"))
    )
    (net (code "39") (name "Net-(JMP8-Pad3)") (class "Default")
      (node (ref "JMP8") (pin "3") (pinfunction "3_3") (pintype "passive"))
      (node (ref "PCB1") (pin "6") (pinfunction "6_6") (pintype "bidirectional"))
    )
    (net (code "40") (name "Net-(JMP9-Pad1)") (class "Default")
      (node (ref "JMP9") (pin "1") (pinfunction "1_1") (pintype "passive"))
      (node (ref "PCB1") (pin "5") (pinfunction "5_5") (pintype "bidirectional"))
    )
    (net (code "41") (name "Net-(JMP9-Pad3)") (class "Default")
      (node (ref "JMP9") (pin "3") (pinfunction "3_3") (pintype "passive"))
      (node (ref "PCB1") (pin "4") (pinfunction "4_4") (pintype "bidirectional"))
    )
    (net (code "42") (name "Net-(JMP10-Pad1)") (class "Default")
      (node (ref "JMP10") (pin "1") (pinfunction "1_1") (pintype "passive"))
      (node (ref "PCB1") (pin "3") (pinfunction "3_3") (pintype "bidirectional"))
    )
    (net (code "43") (name "Net-(JMP10-Pad3)") (class "Default")
      (node (ref "JMP10") (pin "3") (pinfunction "3_3") (pintype "passive"))
      (node (ref "PCB1") (pin "2") (pinfunction "2_2") (pintype "bidirectional"))
    )
    (net (code "44") (name "Net-(Q1-PadG)") (class "Default")
      (node (ref "Q1") (pin "G") (pinfunction "G_G") (pintype "passive"))
      (node (ref "R26") (pin "1") (pinfunction "1_1") (pintype "passive"))
    )
    (net (code "45") (name "Net-(Q2-PadG)") (class "Default")
      (node (ref "Q2") (pin "G") (pinfunction "G_G") (pintype "passive"))
      (node (ref "R29") (pin "1") (pinfunction "1_1") (pintype "passive"))
    )
    (net (code "46") (name "Net-(Q3-PadG)") (class "Default")
      (node (ref "Q3") (pin "G") (pinfunction "G_G") (pintype "passive"))
      (node (ref "R27") (pin "1") (pinfunction "1_1") (pintype "passive"))
    )
    (net (code "47") (name "Net-(Q4-PadG)") (class "Default")
      (node (ref "Q4") (pin "G") (pinfunction "G_G") (pintype "passive"))
      (node (ref "R28") (pin "1") (pinfunction "1_1") (pintype "passive"))
    )
    (net (code "48") (name "Net-(Q5-PadG)") (class "Default")
      (node (ref "Q5") (pin "G") (pinfunction "G_G") (pintype "passive"))
      (node (ref "R43") (pin "1") (pinfunction "1_1") (pintype "passive"))
    )
    (net (code "49") (name "Net-(Q6-PadG)") (class "Default")
      (node (ref "Q6") (pin "G") (pinfunction "G_G") (pintype "passive"))
      (node (ref "R46") (pin "1") (pinfunction "1_1") (pintype "passive"))
    )
    (net (code "50") (name "Net-(Q7-PadG)") (class "Default")
      (node (ref "Q7") (pin "G") (pinfunction "G_G") (pintype "passive"))
      (node (ref "R44") (pin "1") (pinfunction "1_1") (pintype "passive"))
    )
    (net (code "51") (name "Net-(Q8-PadG)") (class "Default")
      (node (ref "Q8") (pin "G") (pinfunction "G_G") (pintype "passive"))
      (node (ref "R45") (pin "1") (pinfunction "1_1") (pintype "passive"))
    )
    (net (code "52") (name "Net-(U$1-1-BH2)") (class "Default")
      (node (ref "C18") (pin "1") (pinfunction "1_1") (pintype "passive"))
      (node (ref "U$1") (pin "1") (pinfunction "1-BH2_1") (pintype "bidirectional"))
    )
    (net (code "53") (name "Net-(U$1-2-GH2)") (class "Default")
      (node (ref "R26") (pin "2") (pinfunction "2_2") (pintype "passive"))
      (node (ref "U$1") (pin "2") (pinfunction "2-GH2_2") (pintype "bidirectional"))
    )
    (net (code "54") (name "Net-(U$1-3-SH2)") (class "Default")
      (node (ref "C18") (pin "2") (pinfunction "2_2") (pintype "passive"))
      (node (ref "R56") (pin "2") (pinfunction "2_2") (pintype "passive"))
      (node (ref "U$1") (pin "3") (pinfunction "3-SH2_3") (pintype "bidirectional"))
    )
    (net (code "55") (name "Net-(U$1-4-GL2)") (class "Default")
      (node (ref "R29") (pin "2") (pinfunction "2_2") (pintype "passive"))
      (node (ref "U$1") (pin "4") (pinfunction "4-GL2_4") (pintype "bidirectional"))
    )
    (net (code "56") (name "Net-(U$1-5-VDH)") (class "Default")
      (node (ref "R25") (pin "1") (pinfunction "1_1") (pintype "passive"))
      (node (ref "U$1") (pin "5") (pinfunction "5-VDH_5") (pintype "bidirectional"))
    )
    (net (code "57") (name "Net-(U$1-8-VREG)") (class "Default")
      (node (ref "C16") (pin "2") (pinfunction "2_2") (pintype "passive"))
      (node (ref "C17") (pin "2") (pinfunction "2_2") (pintype "passive"))
      (node (ref "U$1") (pin "8") (pinfunction "8-VREG_8") (pintype "bidirectional"))
    )
    (net (code "58") (name "Net-(U$1-9-ENA)") (class "Default")
      (node (ref "R22") (pin "2") (pinfunction "2_2") (pintype "passive"))
      (node (ref "U$1") (pin "9") (pinfunction "9-ENA_9") (pintype "bidirectional"))
    )
    (net (code "59") (name "Net-(U$1-13-DT)") (class "Default")
      (node (ref "R21") (pin "2") (pinfunction "2_2") (pintype "passive"))
      (node (ref "U$1") (pin "13") (pinfunction "13-DT_13") (pintype "bidirectional"))
    )
    (net (code "60") (name "Net-(U$1-15-PWM)") (class "Default")
      (node (ref "JMP7") (pin "2") (pinfunction "2_2") (pintype "passive"))
      (node (ref "U$1") (pin "15") (pinfunction "15-PWM_15") (pintype "bidirectional"))
    )
    (net (code "61") (name "Net-(U$1-16-DIR)") (class "Default")
      (node (ref "JMP8") (pin "2") (pinfunction "2_2") (pintype "passive"))
      (node (ref "U$1") (pin "16") (pinfunction "16-DIR_16") (pintype "bidirectional"))
    )
    (net (code "62") (name "Net-(U$1-18-SCDL)") (class "Default")
      (node (ref "R23") (pin "2") (pinfunction "2_2") (pintype "passive"))
      (node (ref "R24") (pin "1") (pinfunction "1_1") (pintype "passive"))
      (node (ref "U$1") (pin "18") (pinfunction "18-SCDL_18") (pintype "bidirectional"))
    )
    (net (code "63") (name "Net-(U$1-20-SL)") (class "Default")
      (node (ref "Q2") (pin "S") (pinfunction "S_S") (pintype "passive"))
      (node (ref "Q4") (pin "S") (pinfunction "S_S") (pintype "passive"))
      (node (ref "R30") (pin "1") (pinfunction "1_1") (pintype "passive"))
      (node (ref "R31") (pin "1") (pinfunction "1_1") (pintype "passive"))
      (node (ref "U$1") (pin "20") (pinfunction "20-SL_20") (pintype "bidirectional"))
    )
    (net (code "64") (name "Net-(U$1-21-GL1)") (class "Default")
      (node (ref "R28") (pin "2") (pinfunction "2_2") (pintype "passive"))
      (node (ref "U$1") (pin "21") (pinfunction "21-GL1_21") (pintype "bidirectional"))
    )
    (net (code "65") (name "Net-(U$1-22-SH1)") (class "Default")
      (node (ref "C23") (pin "2") (pinfunction "2_2") (pintype "passive"))
      (node (ref "R57") (pin "2") (pinfunction "2_2") (pintype "passive"))
      (node (ref "U$1") (pin "22") (pinfunction "22-SH1_22") (pintype "bidirectional"))
    )
    (net (code "66") (name "Net-(U$1-23-GH1)") (class "Default")
      (node (ref "R27") (pin "2") (pinfunction "2_2") (pintype "passive"))
      (node (ref "U$1") (pin "23") (pinfunction "23-GH1_23") (pintype "bidirectional"))
    )
    (net (code "67") (name "Net-(U$1-24-BH1)") (class "Default")
      (node (ref "C23") (pin "1") (pinfunction "1_1") (pintype "passive"))
      (node (ref "U$1") (pin "24") (pinfunction "24-BH1_24") (pintype "bidirectional"))
    )
    (net (code "68") (name "Net-(U$2-1-BH2)") (class "Default")
      (node (ref "C28") (pin "1") (pinfunction "1_1") (pintype "passive"))
      (node (ref "U$2") (pin "1") (pinfunction "1-BH2_1") (pintype "bidirectional"))
    )
    (net (code "69") (name "Net-(U$2-2-GH2)") (class "Default")
      (node (ref "R43") (pin "2") (pinfunction "2_2") (pintype "passive"))
      (node (ref "U$2") (pin "2") (pinfunction "2-GH2_2") (pintype "bidirectional"))
    )
    (net (code "70") (name "Net-(U$2-3-SH2)") (class "Default")
      (node (ref "C28") (pin "2") (pinfunction "2_2") (pintype "passive"))
      (node (ref "R55") (pin "2") (pinfunction "2_2") (pintype "passive"))
      (node (ref "U$2") (pin "3") (pinfunction "3-SH2_3") (pintype "bidirectional"))
    )
    (net (code "71") (name "Net-(U$2-4-GL2)") (class "Default")
      (node (ref "R46") (pin "2") (pinfunction "2_2") (pintype "passive"))
      (node (ref "U$2") (pin "4") (pinfunction "4-GL2_4") (pintype "bidirectional"))
    )
    (net (code "72") (name "Net-(U$2-5-VDH)") (class "Default")
      (node (ref "R42") (pin "1") (pinfunction "1_1") (pintype "passive"))
      (node (ref "U$2") (pin "5") (pinfunction "5-VDH_5") (pintype "bidirectional"))
    )
    (net (code "73") (name "Net-(U$2-8-VREG)") (class "Default")
      (node (ref "C26") (pin "2") (pinfunction "2_2") (pintype "passive"))
      (node (ref "C27") (pin "2") (pinfunction "2_2") (pintype "passive"))
      (node (ref "U$2") (pin "8") (pinfunction "8-VREG_8") (pintype "bidirectional"))
    )
    (net (code "74") (name "Net-(U$2-9-ENA)") (class "Default")
      (node (ref "R39") (pin "2") (pinfunction "2_2") (pintype "passive"))
      (node (ref "U$2") (pin "9") (pinfunction "9-ENA_9") (pintype "bidirectional"))
    )
    (net (code "75") (name "Net-(U$2-13-DT)") (class "Default")
      (node (ref "R38") (pin "2") (pinfunction "2_2") (pintype "passive"))
      (node (ref "U$2") (pin "13") (pinfunction "13-DT_13") (pintype "bidirectional"))
    )
    (net (code "76") (name "Net-(U$2-15-PWM)") (class "Default")
      (node (ref "JMP9") (pin "2") (pinfunction "2_2") (pintype "passive"))
      (node (ref "U$2") (pin "15") (pinfunction "15-PWM_15") (pintype "bidirectional"))
    )
    (net (code "77") (name "Net-(U$2-16-DIR)") (class "Default")
      (node (ref "JMP10") (pin "2") (pinfunction "2_2") (pintype "passive"))
      (node (ref "U$2") (pin "16") (pinfunction "16-DIR_16") (pintype "bidirectional"))
    )
    (net (code "78") (name "Net-(U$2-18-SCDL)") (class "Default")
      (node (ref "R40") (pin "2") (pinfunction "2_2") (pintype "passive"))
      (node (ref "R41") (pin "1") (pinfunction "1_1") (pintype "passive"))
      (node (ref "U$2") (pin "18") (pinfunction "18-SCDL_18") (pintype "bidirectional"))
    )
    (net (code "79") (name "Net-(U$2-20-SL)") (class "Default")
      (node (ref "Q6") (pin "S") (pinfunction "S_S") (pintype "passive"))
      (node (ref "Q8") (pin "S") (pinfunction "S_S") (pintype "passive"))
      (node (ref "R47") (pin "1") (pinfunction "1_1") (pintype "passive"))
      (node (ref "R48") (pin "1") (pinfunction "1_1") (pintype "passive"))
      (node (ref "U$2") (pin "20") (pinfunction "20-SL_20") (pintype "bidirectional"))
    )
    (net (code "80") (name "Net-(U$2-21-GL1)") (class "Default")
      (node (ref "R45") (pin "2") (pinfunction "2_2") (pintype "passive"))
      (node (ref "U$2") (pin "21") (pinfunction "21-GL1_21") (pintype "bidirectional"))
    )
    (net (code "81") (name "Net-(U$2-22-SH1)") (class "Default")
      (node (ref "C33") (pin "2") (pinfunction "2_2") (pintype "passive"))
      (node (ref "R58") (pin "2") (pinfunction "2_2") (pintype "passive"))
      (node (ref "U$2") (pin "22") (pinfunction "22-SH1_22") (pintype "bidirectional"))
    )
    (net (code "82") (name "Net-(U$2-23-GH1)") (class "Default")
      (node (ref "R44") (pin "2") (pinfunction "2_2") (pintype "passive"))
      (node (ref "U$2") (pin "23") (pinfunction "23-GH1_23") (pintype "bidirectional"))
    )
    (net (code "83") (name "Net-(U$2-24-BH1)") (class "Default")
      (node (ref "C33") (pin "1") (pinfunction "1_1") (pintype "passive"))
      (node (ref "U$2") (pin "24") (pinfunction "24-BH1_24") (pintype "bidirectional"))
    )
    (net (code "84") (name "Net-(U2-+IN_A)") (class "Default")
      (node (ref "C2") (pin "2") (pinfunction "2_2") (pintype "passive"))
      (node (ref "R1") (pin "1") (pinfunction "1_1") (pintype "passive"))
      (node (ref "U2") (pin "3") (pinfunction "+IN_A_3") (pintype "input"))
      (node (ref "U2") (pin "5") (pinfunction "+IN_B_5") (pintype "input"))
      (node (ref "X5") (pin "1") (pinfunction "KL_1") (pintype "passive"))
    )
    (net (code "85") (name "Net-(U2-+IN_C)") (class "Default")
      (node (ref "C1") (pin "1") (pinfunction "1_1") (pintype "passive"))
      (node (ref "R16") (pin "1") (pinfunction "1_1") (pintype "passive"))
      (node (ref "U2") (pin "10") (pinfunction "+IN_C_10") (pintype "input"))
      (node (ref "U2") (pin "12") (pinfunction "+IN_D_12") (pintype "input"))
      (node (ref "X4") (pin "1") (pinfunction "KL_1") (pintype "passive"))
    )
    (net (code "86") (name "Net-(U2--IN_A)") (class "Default")
      (node (ref "R2") (pin "1") (pinfunction "1_1") (pintype "passive"))
      (node (ref "R3") (pin "2") (pinfunction "2_2") (pintype "passive"))
      (node (ref "R4") (pin "2") (pinfunction "2_2") (pintype "passive"))
      (node (ref "R5") (pin "2") (pinfunction "2_2") (pintype "passive"))
      (node (ref "U2") (pin "2") (pinfunction "-IN_A_2") (pintype "input"))
    )
    (net (code "87") (name "Net-(U2--IN_B)") (class "Default")
      (node (ref "JMP2") (pin "2") (pinfunction "2_2") (pintype "passive"))
      (node (ref "U2") (pin "6") (pinfunction "-IN_B_6") (pintype "input"))
      (node (ref "U2") (pin "7") (pinfunction "OUT_B_7") (pintype "output"))
    )
    (net (code "88") (name "Net-(U2--IN_C)") (class "Default")
      (node (ref "R17") (pin "1") (pinfunction "1_1") (pintype "passive"))
      (node (ref "R18") (pin "2") (pinfunction "2_2") (pintype "passive"))
      (node (ref "R19") (pin "2") (pinfunction "2_2") (pintype "passive"))
      (node (ref "R20") (pin "2") (pinfunction "2_2") (pintype "passive"))
      (node (ref "U2") (pin "9") (pinfunction "-IN_C_9") (pintype "input"))
    )
    (net (code "89") (name "Net-(U2--IN_D)") (class "Default")
      (node (ref "JMP6") (pin "2") (pinfunction "2_2") (pintype "passive"))
      (node (ref "U2") (pin "13") (pinfunction "-IN_D_13") (pintype "input"))
      (node (ref "U2") (pin "14") (pinfunction "OUT_D_14") (pintype "output"))
    )
    (net (code "90") (name "Net-(U2-OUT_A)") (class "Default")
      (node (ref "R5") (pin "1") (pinfunction "1_1") (pintype "passive"))
      (node (ref "R7") (pin "1") (pinfunction "1_1") (pintype "passive"))
      (node (ref "U2") (pin "1") (pinfunction "OUT_A_1") (pintype "output"))
    )
    (net (code "91") (name "Net-(U2-OUT_C)") (class "Default")
      (node (ref "R13") (pin "1") (pinfunction "1_1") (pintype "passive"))
      (node (ref "R20") (pin "1") (pinfunction "1_1") (pintype "passive"))
      (node (ref "U2") (pin "8") (pinfunction "OUT_C_8") (pintype "output"))
    )
    (net (code "92") (name "Net-(U3-EN)") (class "Default")
      (node (ref "C8") (pin "+") (pinfunction "+_+") (pintype "passive"))
      (node (ref "R9") (pin "1") (pinfunction "1_1") (pintype "passive"))
      (node (ref "U3") (pin "1") (pinfunction "VIN_1") (pintype "power_in"))
      (node (ref "U3") (pin "2") (pinfunction "EN_2") (pintype "input"))
    )
    (net (code "93") (name "Net-(U3-FILT)") (class "Default")
      (node (ref "C5") (pin "1") (pinfunction "1_1") (pintype "passive"))
      (node (ref "U3") (pin "4") (pinfunction "FILT_4") (pintype "passive"))
    )
    (net (code "94") (name "Net-(U3-SS)") (class "Default")
      (node (ref "R6") (pin "1") (pinfunction "1_1") (pintype "passive"))
      (node (ref "U3") (pin "3") (pinfunction "SS_3") (pintype "input"))
    )
    (net (code "95") (name "Net-(X1A-KL)") (class "Default")
      (node (ref "Q7") (pin "S") (pinfunction "S_S") (pintype "passive"))
      (node (ref "Q8") (pin "D") (pinfunction "D_D") (pintype "passive"))
      (node (ref "R58") (pin "1") (pinfunction "1_1") (pintype "passive"))
      (node (ref "X1") (pin "1") (pinfunction "KL_1") (pintype "passive"))
    )
    (net (code "96") (name "Net-(X1C-KL)") (class "Default")
      (node (ref "Q5") (pin "S") (pinfunction "S_S") (pintype "passive"))
      (node (ref "Q6") (pin "D") (pinfunction "D_D") (pintype "passive"))
      (node (ref "R55") (pin "1") (pinfunction "1_1") (pintype "passive"))
      (node (ref "X1") (pin "3") (pinfunction "KL_3") (pintype "passive"))
    )
    (net (code "97") (name "Net-(X3A-KL)") (class "Default")
      (node (ref "Q3") (pin "S") (pinfunction "S_S") (pintype "passive"))
      (node (ref "Q4") (pin "D") (pinfunction "D_D") (pintype "passive"))
      (node (ref "R57") (pin "1") (pinfunction "1_1") (pintype "passive"))
      (node (ref "X3") (pin "1") (pinfunction "KL_1") (pintype "passive"))
    )
    (net (code "98") (name "Net-(X3C-KL)") (class "Default")
      (node (ref "Q1") (pin "S") (pinfunction "S_S") (pintype "passive"))
      (node (ref "Q2") (pin "D") (pinfunction "D_D") (pintype "passive"))
      (node (ref "R56") (pin "1") (pinfunction "1_1") (pintype "passive"))
      (node (ref "X3") (pin "3") (pinfunction "KL_3") (pintype "passive"))
    )
    (net (code "99") (name "unconnected-(PCB1-(N{slash}C)-PadN{slash}C)") (class "Default")
      (node (ref "PCB1") (pin "N/C") (pinfunction "(N/C)_N/C") (pintype "bidirectional"))
    )
    (net (code "100") (name "unconnected-(PCB1-0(RX)-Pad0)") (class "Default")
      (node (ref "PCB1") (pin "0") (pinfunction "0(RX)_0") (pintype "bidirectional"))
    )
    (net (code "101") (name "unconnected-(PCB1-1(TX)-Pad1)") (class "Default")
      (node (ref "PCB1") (pin "1") (pinfunction "1(TX)_1") (pintype "bidirectional"))
    )
    (net (code "102") (name "unconnected-(PCB1-14(TX3)-Pad14)") (class "Default")
      (node (ref "PCB1") (pin "14") (pinfunction "14(TX3)_14") (pintype "bidirectional"))
    )
    (net (code "103") (name "unconnected-(PCB1-15(RX3)-Pad15)") (class "Default")
      (node (ref "PCB1") (pin "15") (pinfunction "15(RX3)_15") (pintype "bidirectional"))
    )
    (net (code "104") (name "unconnected-(PCB1-16(TX2)-Pad16)") (class "Default")
      (node (ref "PCB1") (pin "16") (pinfunction "16(TX2)_16") (pintype "bidirectional"))
    )
    (net (code "105") (name "unconnected-(PCB1-17(RX2)-Pad17)") (class "Default")
      (node (ref "PCB1") (pin "17") (pinfunction "17(RX2)_17") (pintype "bidirectional"))
    )
    (net (code "106") (name "unconnected-(PCB1-18(TX1)-Pad18)") (class "Default")
      (node (ref "PCB1") (pin "18") (pinfunction "18(TX1)_18") (pintype "bidirectional"))
    )
    (net (code "107") (name "unconnected-(PCB1-19(RX1)-Pad19)") (class "Default")
      (node (ref "PCB1") (pin "19") (pinfunction "19(RX1)_19") (pintype "bidirectional"))
    )
    (net (code "108") (name "unconnected-(PCB1-20(SDA)-Pad20)") (class "Default")
      (node (ref "PCB1") (pin "20") (pinfunction "20(SDA)_20") (pintype "bidirectional"))
    )
    (net (code "109") (name "unconnected-(PCB1-21(SCL)-Pad21)") (class "Default")
      (node (ref "PCB1") (pin "21") (pinfunction "21(SCL)_21") (pintype "bidirectional"))
    )
    (net (code "110") (name "unconnected-(PCB1-CANRX-PadA14)") (class "Default")
      (node (ref "PCB1") (pin "A14") (pinfunction "CANRX_A14") (pintype "bidirectional"))
    )
    (net (code "111") (name "unconnected-(PCB1-CANTX-PadA15)") (class "Default")
      (node (ref "PCB1") (pin "A15") (pinfunction "CANTX_A15") (pintype "bidirectional"))
    )
    (net (code "112") (name "unconnected-(PCB1-DAC0-PadA12)") (class "Default")
      (node (ref "PCB1") (pin "A12") (pinfunction "DAC0_A12") (pintype "bidirectional"))
    )
    (net (code "113") (name "unconnected-(PCB1-DAC1-PadA13)") (class "Default")
      (node (ref "PCB1") (pin "A13") (pinfunction "DAC1_A13") (pintype "bidirectional"))
    )
    (net (code "114") (name "unconnected-(PCB1-IOREF-PadI{slash}OREF)") (class "Default")
      (node (ref "PCB1") (pin "I/OREF") (pinfunction "IOREF_I/OREF") (pintype "bidirectional"))
    )
    (net (code "115") (name "unconnected-(PCB1-PadA10)") (class "Default")
      (node (ref "PCB1") (pin "A10") (pinfunction "A10_A10") (pintype "bidirectional"))
    )
    (net (code "116") (name "unconnected-(PCB1-PadA11)") (class "Default")
      (node (ref "PCB1") (pin "A11") (pinfunction "A11_A11") (pintype "bidirectional"))
    )
    (net (code "117") (name "unconnected-(PCB1-PadRESET)") (class "Default")
      (node (ref "PCB1") (pin "RESET") (pinfunction "RESET_RESET") (pintype "bidirectional"))
    )
    (net (code "118") (name "unconnected-(PCB1-PadSCL1)") (class "Default")
      (node (ref "PCB1") (pin "SCL1") (pinfunction "SCL1_SCL1") (pintype "bidirectional"))
    )
    (net (code "119") (name "unconnected-(PCB1-PadSDA1)") (class "Default")
      (node (ref "PCB1") (pin "SDA1") (pinfunction "SDA1_SDA1") (pintype "bidirectional"))
    )
    (net (code "120") (name "unconnected-(PCB1-PadVIN)") (class "Default")
      (node (ref "PCB1") (pin "VIN") (pinfunction "VIN_VIN") (pintype "bidirectional"))
    )
    (net (code "121") (name "unconnected-(R11-PadA)") (class "Default")
      (node (ref "R11") (pin "A") (pinfunction "A_A") (pintype "passive"))
    )
    (net (code "122") (name "unconnected-(R14-PadA)") (class "Default")
      (node (ref "R14") (pin "A") (pinfunction "A_A") (pintype "passive"))
    )
    (net (code "123") (name "unconnected-(U$1-6-RPP-Pad6)") (class "Default")
      (node (ref "U$1") (pin "6") (pinfunction "6-RPP_6") (pintype "bidirectional"))
    )
    (net (code "124") (name "unconnected-(U$1-17-~{ERR}-Pad17)") (class "Default")
      (node (ref "U$1") (pin "17") (pinfunction "17-~{ERR}_17") (pintype "bidirectional"))
    )
    (net (code "125") (name "unconnected-(U$2-6-RPP-Pad6)") (class "Default")
      (node (ref "U$2") (pin "6") (pinfunction "6-RPP_6") (pintype "bidirectional"))
    )
    (net (code "126") (name "unconnected-(U$2-17-~{ERR}-Pad17)") (class "Default")
      (node (ref "U$2") (pin "17") (pinfunction "17-~{ERR}_17") (pintype "bidirectional"))
    )
  )
)
